# led_copy.net
KiCad netlist of a schematic drawn in EAGLE
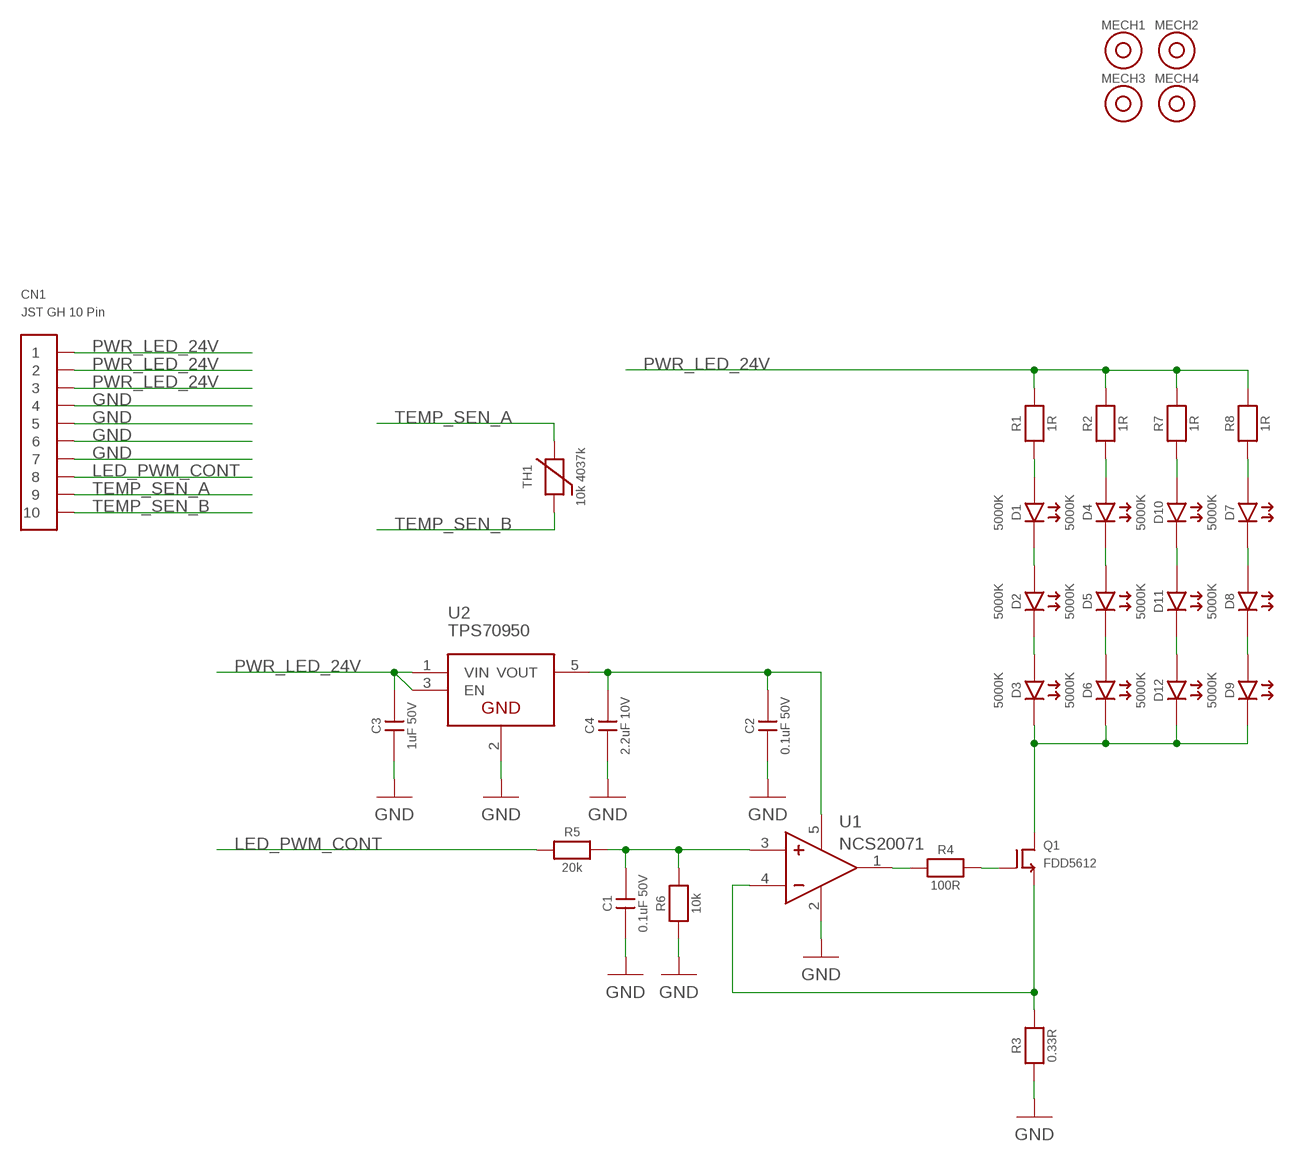
[diagram p0: schematic, sheet 1]

(export (version "E")
  (design (tool "Eeschema 10.0.6"))
  (components
    (comp (ref "C1")
      (value "0.1uF 50V")
      (footprint "eagle-import:0603")
      (fields
        (field (name "MANUFACTURER") "KEMET")
        (field (name "TOLERANCE") "±10%")
        (field (name "VOLTAGE") "50V")
      )
      (libsource (lib "eagle-import") (part "C0603C104K5RAC7081"))
    )
    (comp (ref "C2")
      (value "0.1uF 50V")
      (footprint "eagle-import:0603")
      (fields
        (field (name "MANUFACTURER") "KEMET")
        (field (name "TOLERANCE") "±10%")
        (field (name "VOLTAGE") "50V")
      )
      (libsource (lib "eagle-import") (part "C0603C104K5RAC7081"))
    )
    (comp (ref "C3")
      (value "1uF 50V")
      (footprint "eagle-import:1206")
      (fields
        (field (name "MANUFACTURER") "KEMET")
        (field (name "TOLERANCE") "±10%")
        (field (name "VOLTAGE") "50V")
      )
      (libsource (lib "eagle-import") (part "C1206C105K5RACAUTO"))
    )
    (comp (ref "C4")
      (value "2.2uF 10V")
      (footprint "eagle-import:0603")
      (fields
        (field (name "MANUFACTURER") "Samsung Electro-Mechanics")
        (field (name "TOLERANCE") "±10%")
        (field (name "VOLTAGE") "10V")
      )
      (libsource (lib "eagle-import") (part "CL10B225KP8NFNC"))
    )
    (comp (ref "CN1")
      (value "JST GH 10 Pin")
      (footprint "eagle-import:1.25-10PWT")
      (libsource (lib "eagle-import") (part "1.25-10PWT"))
    )
    (comp (ref "D1")
      (value "5000K")
      (footprint "eagle-import:LH502C")
      (libsource (lib "eagle-import") (part "SPHWH1L5N605YER3A4"))
    )
    (comp (ref "D2")
      (value "5000K")
      (footprint "eagle-import:LH502C")
      (libsource (lib "eagle-import") (part "SPHWH1L5N605YER3A4"))
    )
    (comp (ref "D3")
      (value "5000K")
      (footprint "eagle-import:LH502C")
      (libsource (lib "eagle-import") (part "SPHWH1L5N605YER3A4"))
    )
    (comp (ref "D4")
      (value "5000K")
      (footprint "eagle-import:LH502C")
      (libsource (lib "eagle-import") (part "SPHWH1L5N605YER3A4"))
    )
    (comp (ref "D5")
      (value "5000K")
      (footprint "eagle-import:LH502C")
      (libsource (lib "eagle-import") (part "SPHWH1L5N605YER3A4"))
    )
    (comp (ref "D6")
      (value "5000K")
      (footprint "eagle-import:LH502C")
      (libsource (lib "eagle-import") (part "SPHWH1L5N605YER3A4"))
    )
    (comp (ref "D7")
      (value "5000K")
      (footprint "eagle-import:LH502C")
      (libsource (lib "eagle-import") (part "SPHWH1L5N605YER3A4"))
    )
    (comp (ref "D8")
      (value "5000K")
      (footprint "eagle-import:LH502C")
      (libsource (lib "eagle-import") (part "SPHWH1L5N605YER3A4"))
    )
    (comp (ref "D9")
      (value "5000K")
      (footprint "eagle-import:LH502C")
      (libsource (lib "eagle-import") (part "SPHWH1L5N605YER3A4"))
    )
    (comp (ref "D10")
      (value "5000K")
      (footprint "eagle-import:LH502C")
      (libsource (lib "eagle-import") (part "SPHWH1L5N605YER3A4"))
    )
    (comp (ref "D11")
      (value "5000K")
      (footprint "eagle-import:LH502C")
      (libsource (lib "eagle-import") (part "SPHWH1L5N605YER3A4"))
    )
    (comp (ref "D12")
      (value "5000K")
      (footprint "eagle-import:LH502C")
      (libsource (lib "eagle-import") (part "SPHWH1L5N605YER3A4"))
    )
    (comp (ref "MECH1")
      (value "6mm x 3mm")
      (footprint "eagle-import:MOUNTHOLE_6X3")
      (libsource (lib "eagle-import") (part "MOUNTHOLE"))
    )
    (comp (ref "MECH2")
      (value "6mm x 3mm")
      (footprint "eagle-import:MOUNTHOLE_6X3")
      (libsource (lib "eagle-import") (part "MOUNTHOLE"))
    )
    (comp (ref "MECH3")
      (value "6mm x 3mm")
      (footprint "eagle-import:MOUNTHOLE_6X3")
      (libsource (lib "eagle-import") (part "MOUNTHOLE"))
    )
    (comp (ref "MECH4")
      (value "6mm x 3mm")
      (footprint "eagle-import:MOUNTHOLE_6X3")
      (libsource (lib "eagle-import") (part "MOUNTHOLE"))
    )
    (comp (ref "Q1")
      (value "FDD5612")
      (footprint "eagle-import:TO252")
      (libsource (lib "eagle-import") (part "FDD5612"))
    )
    (comp (ref "R1")
      (value "1R")
      (footprint "eagle-import:1206")
      (libsource (lib "eagle-import") (part "CRCW12061R00FKEA"))
    )
    (comp (ref "R2")
      (value "1R")
      (footprint "eagle-import:1206")
      (libsource (lib "eagle-import") (part "CRCW12061R00FKEA"))
    )
    (comp (ref "R3")
      (value "0.33R")
      (footprint "eagle-import:0603")
      (libsource (lib "eagle-import") (part "CRL0603-FW-R330ELF"))
    )
    (comp (ref "R4")
      (value "100R")
      (footprint "eagle-import:0603")
      (fields
        (field (name "MANUFACTURER") "Vishay Dale")
        (field (name "POWER") "0.1W, 1/10W")
        (field (name "TOLERANCE") "±1%")
      )
      (libsource (lib "eagle-import") (part "CRCW0603100RFKEC"))
    )
    (comp (ref "R5")
      (value "20k")
      (footprint "eagle-import:0603")
      (fields
        (field (name "MANUFACTURER") "Vishay Dale")
        (field (name "POWER") "0.1W, 1/10W")
        (field (name "TOLERANCE") "±1%")
      )
      (libsource (lib "eagle-import") (part "CRCW060320K0FKEA"))
    )
    (comp (ref "R6")
      (value "10k")
      (footprint "eagle-import:0603")
      (fields
        (field (name "MANUFACTURER") "Vishay Dale")
        (field (name "POWER") "0.1W, 1/10W")
        (field (name "TOLERANCE") "±1%")
      )
      (libsource (lib "eagle-import") (part "CRCW060310K0FKTA"))
    )
    (comp (ref "R7")
      (value "1R")
      (footprint "eagle-import:1206")
      (libsource (lib "eagle-import") (part "CRCW12061R00FKEA"))
    )
    (comp (ref "R8")
      (value "1R")
      (footprint "eagle-import:1206")
      (libsource (lib "eagle-import") (part "CRCW12061R00FKEA"))
    )
    (comp (ref "TH1")
      (value "10k 4037k")
      (footprint "eagle-import:0603")
      (libsource (lib "eagle-import") (part "NTCG164BF103HT1"))
    )
    (comp (ref "U1")
      (value "NCS20071")
      (footprint "eagle-import:SOT23-5")
      (libsource (lib "eagle-import") (part "NCS20071SN2T1G"))
    )
    (comp (ref "U2")
      (value "TPS70950")
      (footprint "eagle-import:SOT23-5")
      (libsource (lib "eagle-import") (part "TPS70950DBVT"))
    )
  )
  (nets
    (net (code "1") (name "/LED_PWM_CONT") (class "Default")
      (node (ref "CN1") (pin "8") (pinfunction "8_8") (pintype "bidirectional"))
      (node (ref "R5") (pin "1") (pinfunction "1_1") (pintype "bidirectional"))
    )
    (net (code "2") (name "/PWR_LED_24V") (class "Default")
      (node (ref "C3") (pin "2") (pinfunction "2_2") (pintype "bidirectional"))
      (node (ref "CN1") (pin "1") (pinfunction "1_1") (pintype "bidirectional"))
      (node (ref "CN1") (pin "2") (pinfunction "2_2") (pintype "bidirectional"))
      (node (ref "CN1") (pin "3") (pinfunction "3_3") (pintype "bidirectional"))
      (node (ref "R1") (pin "2") (pinfunction "2_2") (pintype "bidirectional"))
      (node (ref "R2") (pin "2") (pinfunction "2_2") (pintype "bidirectional"))
      (node (ref "R7") (pin "2") (pinfunction "2_2") (pintype "bidirectional"))
      (node (ref "R8") (pin "2") (pinfunction "2_2") (pintype "bidirectional"))
      (node (ref "U2") (pin "1") (pinfunction "VIN_1") (pintype "bidirectional"))
      (node (ref "U2") (pin "3") (pinfunction "EN_3") (pintype "bidirectional"))
    )
    (net (code "3") (name "/TEMP_SEN_A") (class "Default")
      (node (ref "CN1") (pin "9") (pinfunction "9_9") (pintype "bidirectional"))
      (node (ref "TH1") (pin "2") (pinfunction "2_2") (pintype "bidirectional"))
    )
    (net (code "4") (name "/TEMP_SEN_B") (class "Default")
      (node (ref "CN1") (pin "10") (pinfunction "10_10") (pintype "bidirectional"))
      (node (ref "TH1") (pin "1") (pinfunction "1_1") (pintype "bidirectional"))
    )
    (net (code "5") (name "GND") (class "Default")
      (node (ref "C1") (pin "1") (pinfunction "1_1") (pintype "bidirectional"))
      (node (ref "C2") (pin "1") (pinfunction "1_1") (pintype "bidirectional"))
      (node (ref "C3") (pin "1") (pinfunction "1_1") (pintype "bidirectional"))
      (node (ref "C4") (pin "1") (pinfunction "1_1") (pintype "bidirectional"))
      (node (ref "CN1") (pin "4") (pinfunction "4_4") (pintype "bidirectional"))
      (node (ref "CN1") (pin "5") (pinfunction "5_5") (pintype "bidirectional"))
      (node (ref "CN1") (pin "6") (pinfunction "6_6") (pintype "bidirectional"))
      (node (ref "CN1") (pin "7") (pinfunction "7_7") (pintype "bidirectional"))
      (node (ref "R3") (pin "1") (pinfunction "1_1") (pintype "bidirectional"))
      (node (ref "R6") (pin "1") (pinfunction "1_1") (pintype "bidirectional"))
      (node (ref "U1") (pin "2") (pinfunction "V-_2") (pintype "bidirectional"))
      (node (ref "U2") (pin "2") (pinfunction "GND_2") (pintype "bidirectional"))
    )
    (net (code "6") (name "Net-(D1-PadA)") (class "Default")
      (node (ref "D1") (pin "A") (pinfunction "A_A") (pintype "bidirectional"))
      (node (ref "R1") (pin "1") (pinfunction "1_1") (pintype "bidirectional"))
    )
    (net (code "7") (name "Net-(D1-PadK)") (class "Default")
      (node (ref "D1") (pin "K") (pinfunction "K_K") (pintype "bidirectional"))
      (node (ref "D2") (pin "A") (pinfunction "A_A") (pintype "bidirectional"))
    )
    (net (code "8") (name "Net-(D2-PadK)") (class "Default")
      (node (ref "D2") (pin "K") (pinfunction "K_K") (pintype "bidirectional"))
      (node (ref "D3") (pin "A") (pinfunction "A_A") (pintype "bidirectional"))
    )
    (net (code "9") (name "Net-(D4-PadA)") (class "Default")
      (node (ref "D4") (pin "A") (pinfunction "A_A") (pintype "bidirectional"))
      (node (ref "R2") (pin "1") (pinfunction "1_1") (pintype "bidirectional"))
    )
    (net (code "10") (name "Net-(D4-PadK)") (class "Default")
      (node (ref "D4") (pin "K") (pinfunction "K_K") (pintype "bidirectional"))
      (node (ref "D5") (pin "A") (pinfunction "A_A") (pintype "bidirectional"))
    )
    (net (code "11") (name "Net-(D5-PadK)") (class "Default")
      (node (ref "D5") (pin "K") (pinfunction "K_K") (pintype "bidirectional"))
      (node (ref "D6") (pin "A") (pinfunction "A_A") (pintype "bidirectional"))
    )
    (net (code "12") (name "Net-(D7-PadA)") (class "Default")
      (node (ref "D7") (pin "A") (pinfunction "A_A") (pintype "bidirectional"))
      (node (ref "R8") (pin "1") (pinfunction "1_1") (pintype "bidirectional"))
    )
    (net (code "13") (name "Net-(D7-PadK)") (class "Default")
      (node (ref "D7") (pin "K") (pinfunction "K_K") (pintype "bidirectional"))
      (node (ref "D8") (pin "A") (pinfunction "A_A") (pintype "bidirectional"))
    )
    (net (code "14") (name "Net-(D8-PadK)") (class "Default")
      (node (ref "D8") (pin "K") (pinfunction "K_K") (pintype "bidirectional"))
      (node (ref "D9") (pin "A") (pinfunction "A_A") (pintype "bidirectional"))
    )
    (net (code "15") (name "Net-(D10-PadA)") (class "Default")
      (node (ref "D10") (pin "A") (pinfunction "A_A") (pintype "bidirectional"))
      (node (ref "R7") (pin "1") (pinfunction "1_1") (pintype "bidirectional"))
    )
    (net (code "16") (name "Net-(D10-PadK)") (class "Default")
      (node (ref "D10") (pin "K") (pinfunction "K_K") (pintype "bidirectional"))
      (node (ref "D11") (pin "A") (pinfunction "A_A") (pintype "bidirectional"))
    )
    (net (code "17") (name "Net-(D11-PadK)") (class "Default")
      (node (ref "D11") (pin "K") (pinfunction "K_K") (pintype "bidirectional"))
      (node (ref "D12") (pin "A") (pinfunction "A_A") (pintype "bidirectional"))
    )
    (net (code "18") (name "Net-(Q1-D)") (class "Default")
      (node (ref "D12") (pin "K") (pinfunction "K_K") (pintype "bidirectional"))
      (node (ref "D3") (pin "K") (pinfunction "K_K") (pintype "bidirectional"))
      (node (ref "D6") (pin "K") (pinfunction "K_K") (pintype "bidirectional"))
      (node (ref "D9") (pin "K") (pinfunction "K_K") (pintype "bidirectional"))
      (node (ref "Q1") (pin "2") (pinfunction "D_2") (pintype "bidirectional"))
    )
    (net (code "19") (name "Net-(Q1-G)") (class "Default")
      (node (ref "Q1") (pin "1") (pinfunction "G_1") (pintype "bidirectional"))
      (node (ref "R4") (pin "2") (pinfunction "2_2") (pintype "bidirectional"))
    )
    (net (code "20") (name "Net-(Q1-S)") (class "Default")
      (node (ref "Q1") (pin "3") (pinfunction "S_3") (pintype "bidirectional"))
      (node (ref "R3") (pin "2") (pinfunction "2_2") (pintype "bidirectional"))
      (node (ref "U1") (pin "4") (pinfunction "-_4") (pintype "bidirectional"))
    )
    (net (code "21") (name "Net-(U1-+)") (class "Default")
      (node (ref "C1") (pin "2") (pinfunction "2_2") (pintype "bidirectional"))
      (node (ref "R5") (pin "2") (pinfunction "2_2") (pintype "bidirectional"))
      (node (ref "R6") (pin "2") (pinfunction "2_2") (pintype "bidirectional"))
      (node (ref "U1") (pin "3") (pinfunction "+_3") (pintype "bidirectional"))
    )
    (net (code "22") (name "Net-(U1-OUT)") (class "Default")
      (node (ref "R4") (pin "1") (pinfunction "1_1") (pintype "bidirectional"))
      (node (ref "U1") (pin "1") (pinfunction "OUT_1") (pintype "bidirectional"))
    )
    (net (code "23") (name "Net-(U1-V+)") (class "Default")
      (node (ref "C2") (pin "2") (pinfunction "2_2") (pintype "bidirectional"))
      (node (ref "C4") (pin "2") (pinfunction "2_2") (pintype "bidirectional"))
      (node (ref "U1") (pin "5") (pinfunction "V+_5") (pintype "bidirectional"))
      (node (ref "U2") (pin "5") (pinfunction "VOUT_5") (pintype "bidirectional"))
    )
  )
)
